# ai_V1_1.net
KiCad netlist of a schematic drawn in Altium Designer
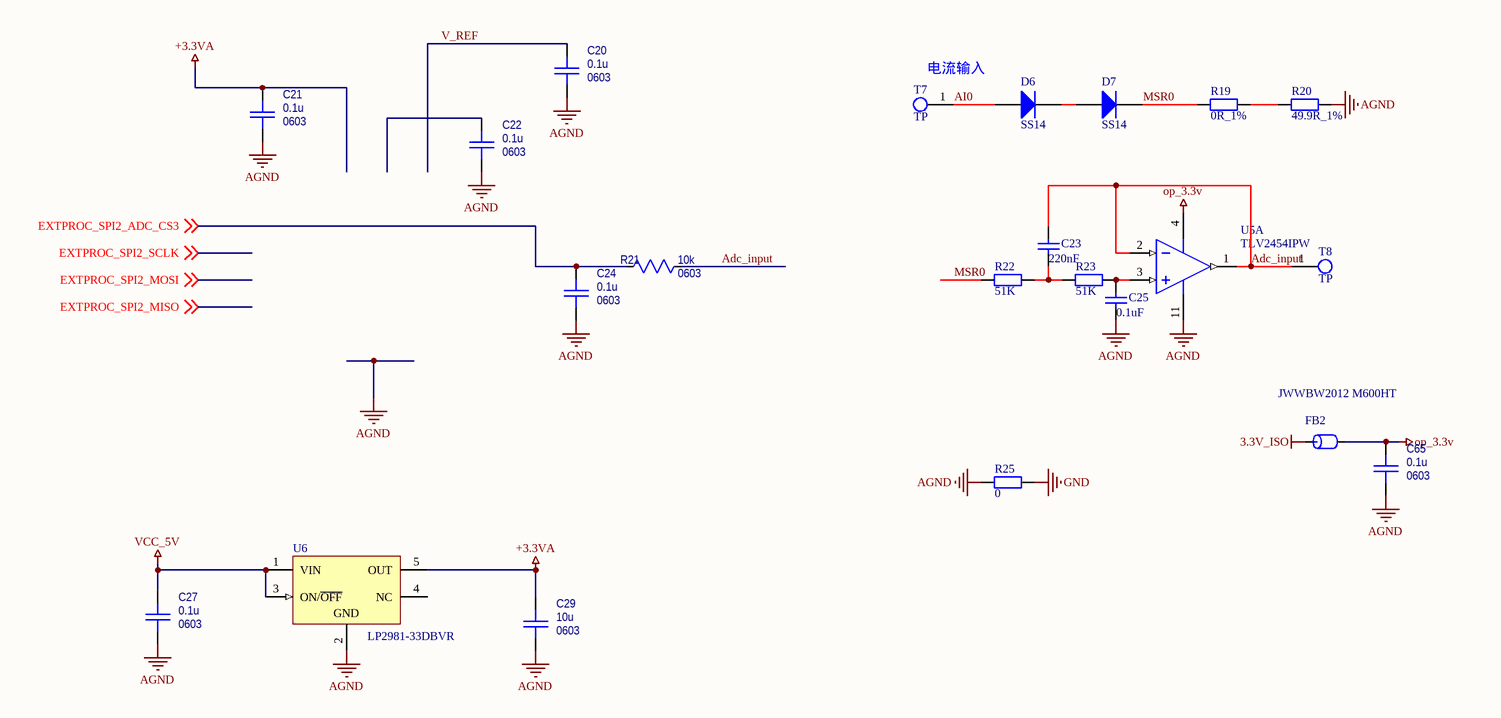
[diagram p0: ai_V1.1.SchDoc]

(export (version "E")
  (design (tool "Eeschema 10.0.6"))
  (components
    (comp (ref "C20")
      (value "0.1u")
      (footprint "CAPC1608X092N_0603")
      (description "Capacitor, MLCC")
      (fields
        (field (name "PARTNUMBER") "C0603C104M5RACTU")
        (field (name "TOLERANCE") "[tol]")
        (field (name "PACKAGE") "0603")
      )
      (libsource (lib "Karl") (part "Capacitor_0603"))
    )
    (comp (ref "C21")
      (value "0.1u")
      (footprint "CAPC1608X092N_0603")
      (description "Capacitor, MLCC")
      (fields
        (field (name "PARTNUMBER") "C0603C104M5RACTU")
        (field (name "TOLERANCE") "[tol]")
        (field (name "PACKAGE") "0603")
      )
      (libsource (lib "Karl") (part "Capacitor_0603"))
    )
    (comp (ref "C22")
      (value "0.1u")
      (footprint "CAPC1608X092N_0603")
      (description "Capacitor, MLCC")
      (fields
        (field (name "PARTNUMBER") "C0603C104M5RACTU")
        (field (name "TOLERANCE") "[tol]")
        (field (name "PACKAGE") "0603")
      )
      (libsource (lib "Karl") (part "Capacitor_0603"))
    )
    (comp (ref "C23")
      (value "220nF")
      (footprint "0805C")
      (description "Capacitor")
      (fields (field (name "PUBLISHER") "Altium Limited"))
      (libsource (lib "Miscellaneous Devices") (part "Cap"))
    )
    (comp (ref "C24")
      (value "0.1u")
      (footprint "CAPC1608X092N_0603")
      (description "Capacitor, MLCC")
      (fields
        (field (name "PARTNUMBER") "C0603C104M5RACTU")
        (field (name "TOLERANCE") "[tol]")
        (field (name "PACKAGE") "0603")
      )
      (libsource (lib "Karl") (part "Capacitor_0603"))
    )
    (comp (ref "C25")
      (value "0.1uF")
      (footprint "0603C")
      (description "Capacitor")
      (fields (field (name "PUBLISHER") "Altium Limited"))
      (libsource (lib "Miscellaneous Devices") (part "Cap"))
    )
    (comp (ref "C27")
      (value "0.1u")
      (footprint "CAPC1608X092N_0603")
      (description "Capacitor, MLCC")
      (fields
        (field (name "PARTNUMBER") "C0603C104M5RACTU")
        (field (name "TOLERANCE") "[tol]")
        (field (name "PACKAGE") "0603")
      )
      (libsource (lib "Karl") (part "Capacitor_0603"))
    )
    (comp (ref "C29")
      (value "10u")
      (footprint "CAPC1608X092N_0603")
      (description "Capacitor, MLCC")
      (fields
        (field (name "PARTNUMBER") "GRM188R61A106KE69D")
        (field (name "TOLERANCE") "[tol]")
        (field (name "PACKAGE") "0603")
      )
      (libsource (lib "Karl") (part "Capacitor_0603"))
    )
    (comp (ref "C65")
      (value "0.1u")
      (footprint "CAPC1608X092N_0603")
      (description "Capacitor, MLCC")
      (fields
        (field (name "PARTNUMBER") "C0603C104M5RACTU")
        (field (name "TOLERANCE") "[tol]")
        (field (name "PACKAGE") "0603")
      )
      (libsource (lib "Karl") (part "Capacitor_0603"))
    )
    (comp (ref "D6")
      (value "SS14")
      (footprint "DO-214AC")
      (description "Default Diode")
      (fields (field (name "PUBLISHER") "Altium Limited"))
      (libsource (lib "Miscellaneous Devices") (part "Diode"))
    )
    (comp (ref "D7")
      (value "SS14")
      (footprint "DO-214AC")
      (description "Default Diode")
      (fields (field (name "PUBLISHER") "Altium Limited"))
      (libsource (lib "Miscellaneous Devices") (part "Diode"))
    )
    (comp (ref "FB2")
      (value "JWWBW2012 M600HT")
      (footprint "0805R")
      (libsource (lib "Schlib_20110825") (part "FB"))
    )
    (comp (ref "R19") (value "0R_1%") (footprint "0805R") (libsource (lib "MQlibrary") (part "Res0805M")))
    (comp (ref "R20") (value "49.9R_1%") (footprint "0805R") (libsource (lib "MQlibrary") (part "Res0805M")))
    (comp (ref "R21")
      (value "10k")
      (footprint "RESC1608X055N_0603")
      (description "Resistor, Standard")
      (fields
        (field (name "PARTNUMBER") "RR0816P-103-D")
        (field (name "TOLERANCE") "tol")
        (field (name "PACKAGE") "0603")
      )
      (libsource (lib "Karl") (part "Resistor_0603"))
    )
    (comp (ref "R22") (value "51K") (footprint "0603R") (libsource (lib "MQlibrary") (part "Res0805M")))
    (comp (ref "R23") (value "51K") (footprint "0603R") (libsource (lib "MQlibrary") (part "Res0805M")))
    (comp (ref "R25") (value "0") (footprint "1206R") (libsource (lib "MQlibrary") (part "Res0805M")))
    (comp (ref "T7") (value "TP") (footprint "TPD") (libsource (lib "Schlib_20110825") (part "TP")))
    (comp (ref "T8") (value "TP") (footprint "TPD") (libsource (lib "Schlib_20110825") (part "TP")))
    (comp (ref "U5")
      (value "TLV2454IPW")
      (footprint "TSSOP14")
      (description "Quad High-speed, Ultra Low-power, Single-Supply TTL comparator")
      (fields (field (name "PUBLISHER") "Altium Limited"))
      (libsource (lib "Maxim Analog Comparator") (part "MAX908EPD"))
    )
    (comp (ref "U6")
      (value "LP2981-33DBVR")
      (footprint "DBV0005A_M")
      (description "Micropower 100 mA Ultra Low-Dropout Regulator, 5-pin SOT-23, Pb-Free")
      (libsource (lib "Bogen") (part "LP2981-33DBVR"))
    )
  )
  (nets
    (net (code "1") (name "+3.3VA") (class "Default")
      (node (ref "C21") (pin "1") (pinfunction "1_1") (pintype "passive"))
      (node (ref "C29") (pin "1") (pinfunction "1_1") (pintype "passive"))
      (node (ref "U6") (pin "5") (pinfunction "OUT_5") (pintype "power_in"))
    )
    (net (code "2") (name "/AI0") (class "Default")
      (node (ref "D6") (pin "1") (pinfunction "A_1") (pintype "passive"))
      (node (ref "T7") (pin "1") (pintype "passive"))
    )
    (net (code "3") (name "/Adc_input") (class "Default")
      (node (ref "C23") (pin "2") (pinfunction "2_2") (pintype "passive"))
      (node (ref "R21") (pin "1") (pinfunction "1_1") (pintype "passive"))
      (node (ref "T8") (pin "1") (pintype "passive"))
      (node (ref "U5") (pin "1") (pinfunction "OUT_1") (pintype "output"))
      (node (ref "U5") (pin "2") (pinfunction "IN-_2") (pintype "input"))
    )
    (net (code "4") (name "/MSR0") (class "Default")
      (node (ref "D7") (pin "2") (pinfunction "K_2") (pintype "passive"))
      (node (ref "R19") (pin "2") (pinfunction "2_2") (pintype "passive"))
      (node (ref "R22") (pin "2") (pinfunction "2_2") (pintype "passive"))
    )
    (net (code "5") (name "/V_REF") (class "Default")
      (node (ref "C20") (pin "1") (pinfunction "1_1") (pintype "passive"))
    )
    (net (code "6") (name "3.3V_ISO") (class "Default") (node (ref "FB2") (pin "1") (pintype "passive")))
    (net (code "7") (name "AGND") (class "Default")
      (node (ref "C20") (pin "2") (pinfunction "2_2") (pintype "passive"))
      (node (ref "C21") (pin "2") (pinfunction "2_2") (pintype "passive"))
      (node (ref "C22") (pin "2") (pinfunction "2_2") (pintype "passive"))
      (node (ref "C24") (pin "2") (pinfunction "2_2") (pintype "passive"))
      (node (ref "C25") (pin "1") (pinfunction "1_1") (pintype "passive"))
      (node (ref "C27") (pin "2") (pinfunction "2_2") (pintype "passive"))
      (node (ref "C29") (pin "2") (pinfunction "2_2") (pintype "passive"))
      (node (ref "C65") (pin "2") (pinfunction "2_2") (pintype "passive"))
      (node (ref "R20") (pin "1") (pinfunction "1_1") (pintype "passive"))
      (node (ref "R25") (pin "2") (pinfunction "2_2") (pintype "passive"))
      (node (ref "U5") (pin "11") (pinfunction "GND_11") (pintype "power_in"))
      (node (ref "U6") (pin "2") (pinfunction "GND_2") (pintype "power_in"))
    )
    (net (code "8") (name "EXTPROC_SPI2_ADC_CS3") (class "Default")
      (node (ref "C24") (pin "1") (pinfunction "1_1") (pintype "passive"))
      (node (ref "R21") (pin "2") (pinfunction "2_2") (pintype "passive"))
    )
    (net (code "12") (name "GND") (class "Default")
      (node (ref "R25") (pin "1") (pinfunction "1_1") (pintype "passive"))
    )
    (net (code "13") (name "Net-(C23-Pad1)") (class "Default")
      (node (ref "C23") (pin "1") (pinfunction "1_1") (pintype "passive"))
      (node (ref "R22") (pin "1") (pinfunction "1_1") (pintype "passive"))
      (node (ref "R23") (pin "2") (pinfunction "2_2") (pintype "passive"))
    )
    (net (code "14") (name "Net-(D6-K)") (class "Default")
      (node (ref "D6") (pin "2") (pinfunction "K_2") (pintype "passive"))
      (node (ref "D7") (pin "1") (pinfunction "A_1") (pintype "passive"))
    )
    (net (code "15") (name "Net-(R19-Pad1)") (class "Default")
      (node (ref "R19") (pin "1") (pinfunction "1_1") (pintype "passive"))
      (node (ref "R20") (pin "2") (pinfunction "2_2") (pintype "passive"))
    )
    (net (code "16") (name "Net-(U5A-IN+)") (class "Default")
      (node (ref "C25") (pin "2") (pinfunction "2_2") (pintype "passive"))
      (node (ref "R23") (pin "1") (pinfunction "1_1") (pintype "passive"))
      (node (ref "U5") (pin "3") (pinfunction "IN+_3") (pintype "input"))
    )
    (net (code "17") (name "VCC_5V") (class "Default")
      (node (ref "C27") (pin "1") (pinfunction "1_1") (pintype "passive"))
      (node (ref "U6") (pin "1") (pinfunction "VIN_1") (pintype "power_in"))
      (node (ref "U6") (pin "3") (pinfunction "ON/~{OFF}_3") (pintype "input"))
    )
    (net (code "18") (name "op_3.3v") (class "Default")
      (node (ref "C65") (pin "1") (pinfunction "1_1") (pintype "passive"))
      (node (ref "FB2") (pin "2") (pintype "passive"))
      (node (ref "U5") (pin "4") (pinfunction "V+_4") (pintype "power_in"))
    )
    (net (code "19") (name "unconnected-(C22-Pad1)") (class "Default")
      (node (ref "C22") (pin "1") (pinfunction "1_1") (pintype "passive"))
    )
    (net (code "20") (name "unconnected-(U6-NC-Pad4)") (class "Default")
      (node (ref "U6") (pin "4") (pinfunction "NC_4") (pintype "passive"))
    )
  )
)
